# 5VRegulator.net
KiCad netlist of a schematic drawn in Altium Designer
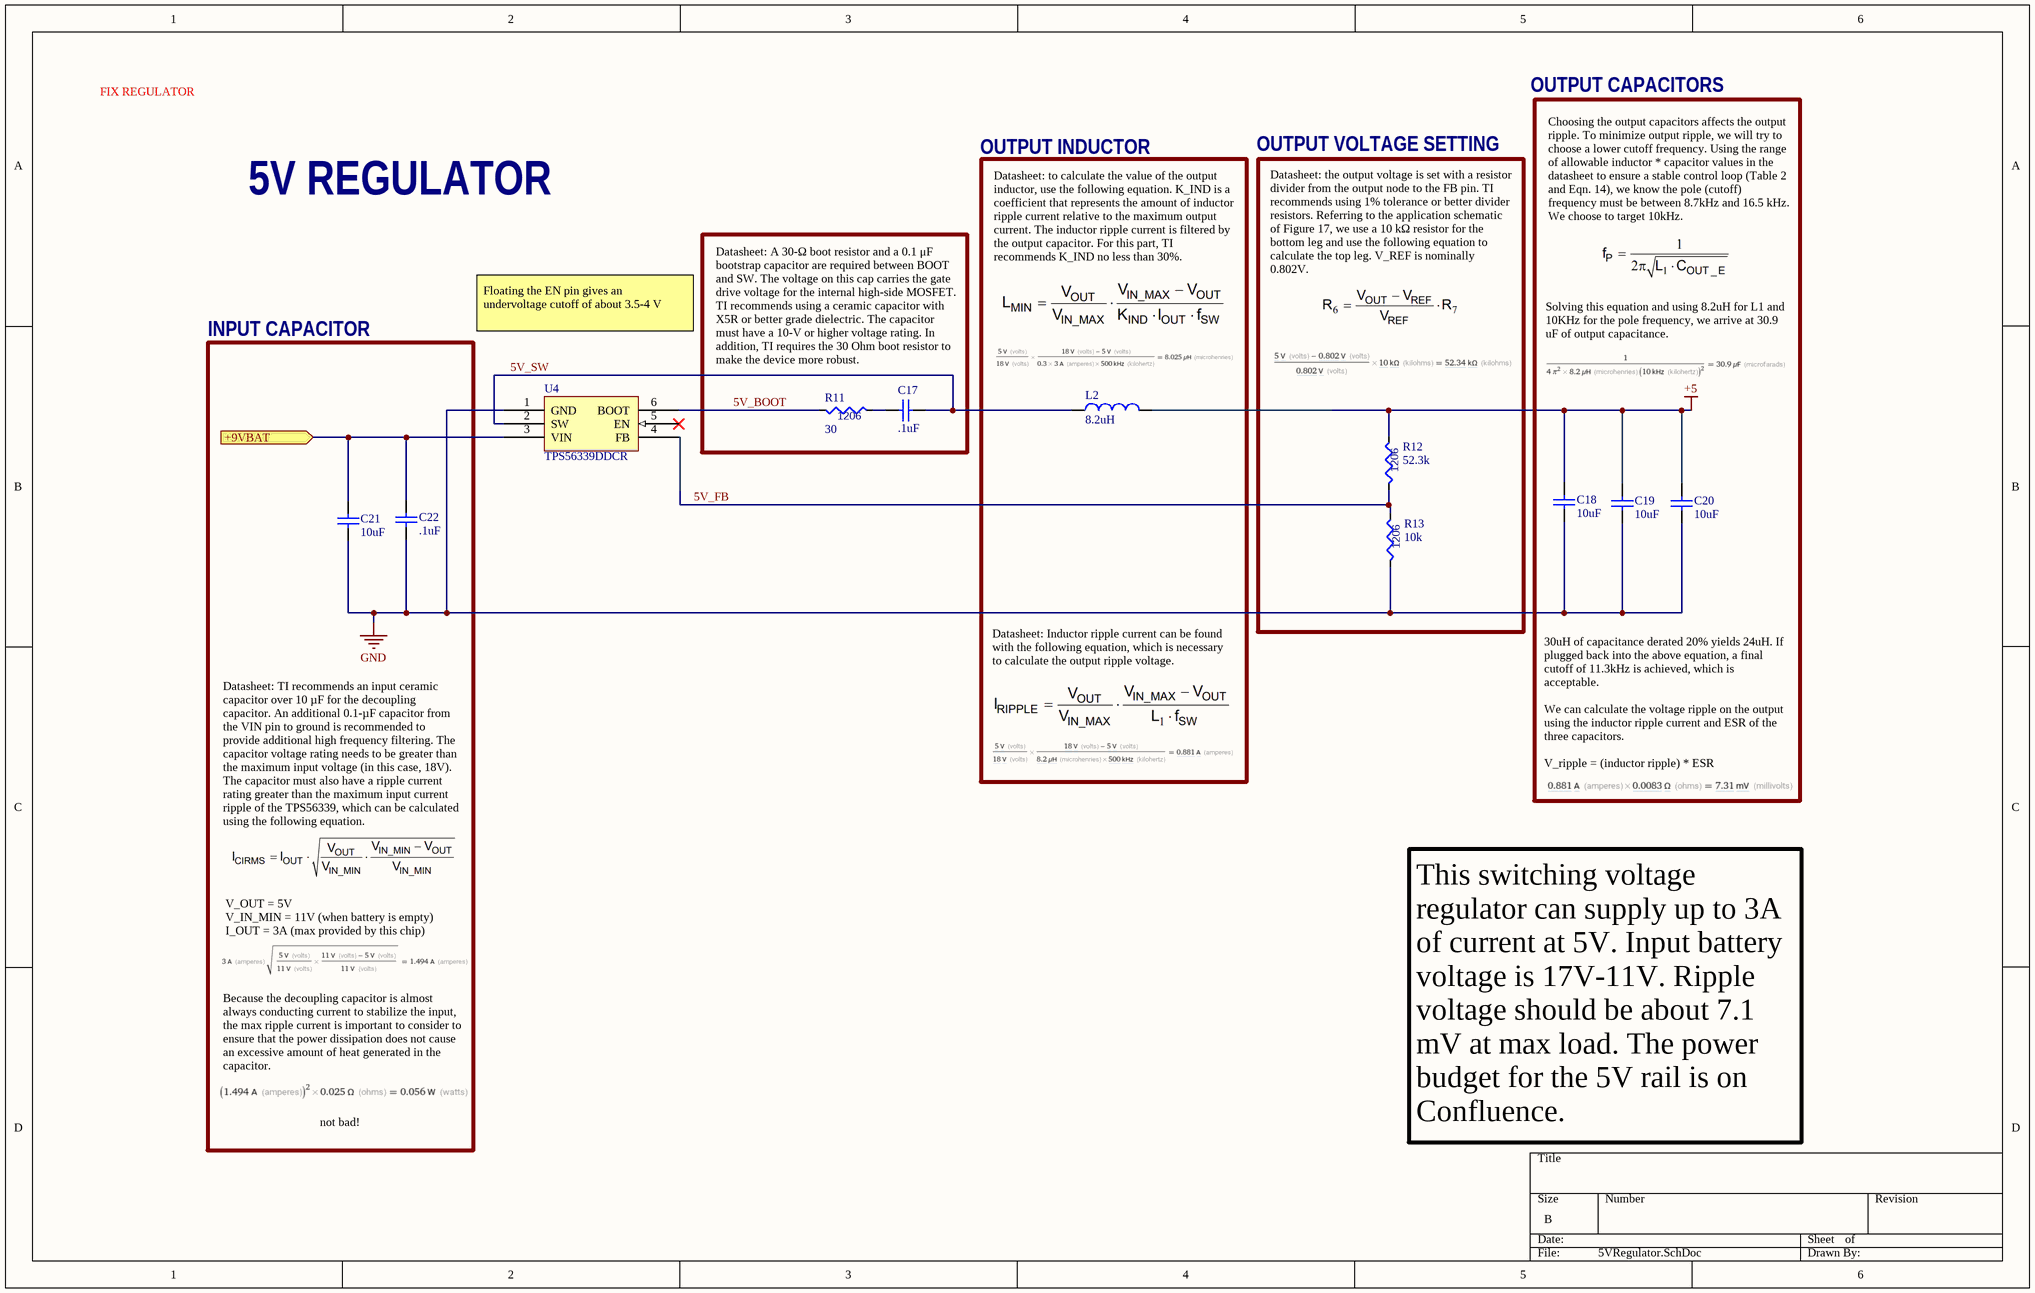
[diagram p0: 5VRegulator.SchDoc]

(export (version "E")
  (design (tool "Eeschema 10.0.6"))
  (components
    (comp (ref "C17")
      (value ".1uF")
      (footprint "Capacitors:C1206")
      (description "CAP CER 0.1UF 50V C0G/NP0 1206")
      (fields (field (name "MADE BY") "Brennan Swanton") (field (name "REVIEWED BY") "Carter Allen"))
      (libsource (lib "Capacitors") (part "CL31B104KBCNNNC"))
    )
    (comp (ref "C18")
      (value "10uF")
      (footprint "Capacitors:C1206")
      (description "CER 10UF 35V X7R 1206")
      (fields (field (name "MADE BY") "Brennan Swanton") (field (name "REVIEWED BY") "Carter Allen"))
      (libsource (lib "Capacitors") (part "CL31B106KLHNNNE"))
    )
    (comp (ref "C19")
      (value "10uF")
      (footprint "Capacitors:C1206")
      (description "CER 10UF 35V X7R 1206")
      (fields (field (name "MADE BY") "Brennan Swanton") (field (name "REVIEWED BY") "Carter Allen"))
      (libsource (lib "Capacitors") (part "CL31B106KLHNNNE"))
    )
    (comp (ref "C20")
      (value "10uF")
      (footprint "Capacitors:C1206")
      (description "CER 10UF 35V X7R 1206")
      (fields (field (name "MADE BY") "Brennan Swanton") (field (name "REVIEWED BY") "Carter Allen"))
      (libsource (lib "Capacitors") (part "CL31B106KLHNNNE"))
    )
    (comp (ref "C21")
      (value "10uF")
      (footprint "Capacitors:C1206")
      (description "CER 10UF 35V X7R 1206")
      (fields (field (name "MADE BY") "Brennan Swanton") (field (name "REVIEWED BY") "Carter Allen"))
      (libsource (lib "Capacitors") (part "CL31B106KLHNNNE"))
    )
    (comp (ref "C22")
      (value ".1uF")
      (footprint "Capacitors:C1206")
      (description "CAP CER 0.1UF 50V C0G/NP0 1206")
      (fields (field (name "MADE BY") "Brennan Swanton") (field (name "REVIEWED BY") "Carter Allen"))
      (libsource (lib "Capacitors") (part "CL31B104KBCNNNC"))
    )
    (comp (ref "L2")
      (value "8.2uH")
      (footprint "EATON_HCMA0703")
      (description "Inductor 8.2uH 4A 20%")
      (libsource (lib "Inductors") (part "HCMA0703-8R2-R"))
    )
    (comp (ref "R11")
      (value "30")
      (footprint "Resistors:R1206")
      (description "RES SMD 30 OHM 0.5% 1/4W 1206")
      (fields (field (name "MADE BY") "Jamie") (field (name "REVIEWED BY") "Raphael"))
      (libsource (lib "Resistors") (part "ERA-8AHD300V"))
    )
    (comp (ref "R12")
      (value "52.3k")
      (footprint "Resistors:R1206")
      (description "RES SMD 52.3K OHM 0.1% 1/4W 1206")
      (fields (field (name "MADE BY") "Raphael Navarro") (field (name "REVIEWED BY") "Jamie Smith"))
      (libsource (lib "Resistors") (part "ERA-8AEB5232V"))
    )
    (comp (ref "R13")
      (value "10k")
      (footprint "Resistors:R1206")
      (description "10K OHM 1% 1/4W 1206")
      (fields (field (name "MADE BY") "Brennan Swanton") (field (name "REVIEWED BY") "Carter Allen"))
      (libsource (lib "Resistors") (part "ERJ-8ENF1002V"))
    )
    (comp (ref "U4")
      (value "TPS56339DDCR")
      (footprint "TSOT-23-6")
      (description "Buck Regulator IC Adj. 3A 4.5V-24V Input")
      (libsource (lib "VoltageRegulators") (part "TPS56339DDCR"))
    )
  )
  (nets
    (net (code "1") (name "+5") (class "Default")
      (node (ref "C18") (pin "2") (pinfunction "2_2") (pintype "passive"))
      (node (ref "C19") (pin "2") (pinfunction "2_2") (pintype "passive"))
      (node (ref "C20") (pin "2") (pinfunction "2_2") (pintype "passive"))
      (node (ref "L2") (pin "2") (pinfunction "2_2") (pintype "passive"))
      (node (ref "R12") (pin "2") (pinfunction "2_2") (pintype "passive"))
    )
    (net (code "2") (name "/+9VBAT") (class "Default")
      (node (ref "C21") (pin "2") (pinfunction "2_2") (pintype "passive"))
      (node (ref "C22") (pin "2") (pinfunction "2_2") (pintype "passive"))
      (node (ref "U4") (pin "3") (pinfunction "VIN_3") (pintype "power_in"))
    )
    (net (code "3") (name "/5V_BOOT") (class "Default")
      (node (ref "R11") (pin "1") (pinfunction "1_1") (pintype "passive"))
      (node (ref "U4") (pin "6") (pinfunction "BOOT_6") (pintype "passive"))
    )
    (net (code "4") (name "/5V_FB") (class "Default")
      (node (ref "R12") (pin "1") (pinfunction "1_1") (pintype "passive"))
      (node (ref "R13") (pin "2") (pinfunction "2_2") (pintype "passive"))
      (node (ref "U4") (pin "4") (pinfunction "FB_4") (pintype "passive"))
    )
    (net (code "5") (name "/5V_SW") (class "Default")
      (node (ref "C17") (pin "2") (pinfunction "2_2") (pintype "passive"))
      (node (ref "L2") (pin "1") (pinfunction "1_1") (pintype "passive"))
      (node (ref "U4") (pin "2") (pinfunction "SW_2") (pintype "power_in"))
    )
    (net (code "6") (name "GND") (class "Default")
      (node (ref "C18") (pin "1") (pinfunction "1_1") (pintype "passive"))
      (node (ref "C19") (pin "1") (pinfunction "1_1") (pintype "passive"))
      (node (ref "C20") (pin "1") (pinfunction "1_1") (pintype "passive"))
      (node (ref "C21") (pin "1") (pinfunction "1_1") (pintype "passive"))
      (node (ref "C22") (pin "1") (pinfunction "1_1") (pintype "passive"))
      (node (ref "R13") (pin "1") (pinfunction "1_1") (pintype "passive"))
      (node (ref "U4") (pin "1") (pinfunction "GND_1") (pintype "power_in"))
    )
    (net (code "7") (name "Net-(C17-Pad1)") (class "Default")
      (node (ref "C17") (pin "1") (pinfunction "1_1") (pintype "passive"))
      (node (ref "R11") (pin "2") (pinfunction "2_2") (pintype "passive"))
    )
    (net (code "8") (name "unconnected-(U4-EN-Pad5)") (class "Default")
      (node (ref "U4") (pin "5") (pinfunction "EN_5") (pintype "input+no_connect"))
    )
  )
)
